# SCH_wiring_diagram_2026-05-13.net
KiCad netlist of a schematic drawn in EasyEDA
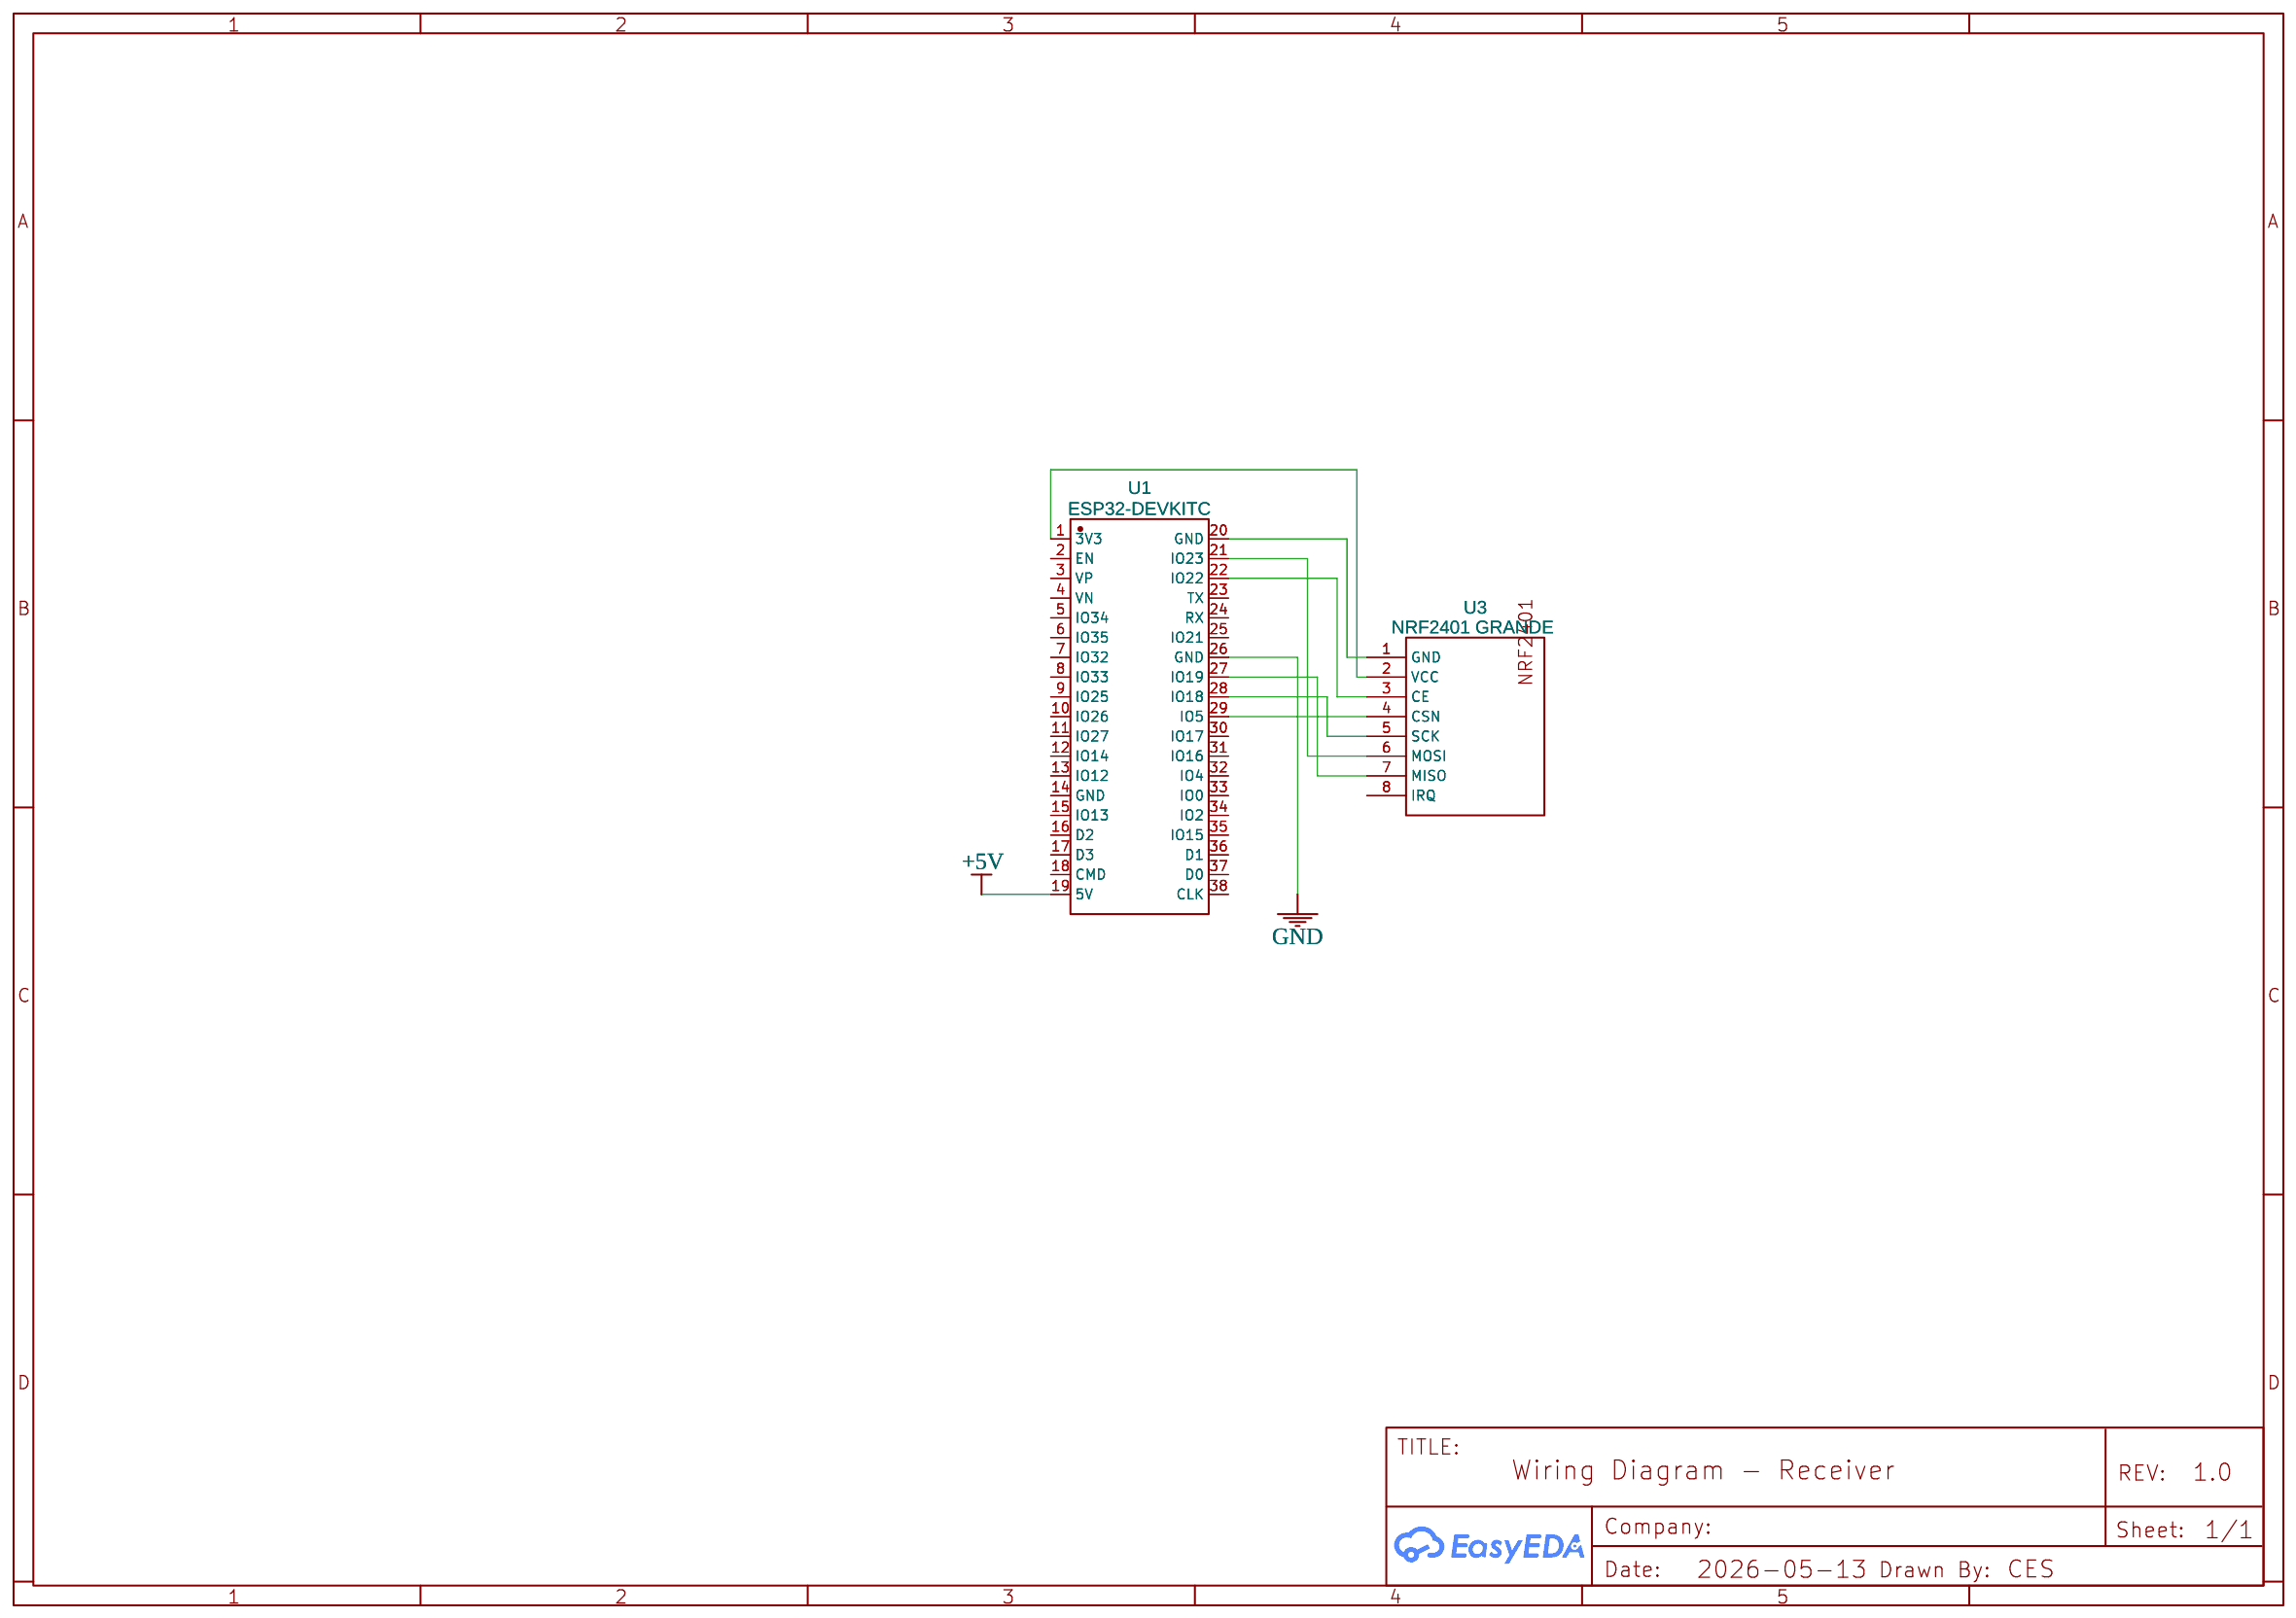
[diagram p0: schematic sheet]

(export (version "E")
  (design (tool "Eeschema 10.0.6"))
  (components
    (comp (ref "U1")
      (value "ESP32-DEVKITC")
      (fields
        (field (name "Manufacturer Part") "ESP32-DevKitC")
        (field (name "Manufacturer") "ESPRESSIF(乐鑫)")
      )
      (libsource (lib "") (part "ESP32-DEVKITC"))
    )
    (comp (ref "U3") (value "NRF2401 GRANDE") (libsource (lib "") (part "NRF2401_GRANDE")))
  )
  (nets
    (net (code "1") (name "+5V") (class "Default")
      (node (ref "U1") (pin "19") (pinfunction "5V_19") (pintype "unspecified"))
    )
    (net (code "2") (name "GND") (class "Default")
      (node (ref "U1") (pin "26") (pinfunction "GND_26") (pintype "unspecified"))
    )
    (net (code "3") (name "Net-(U1-3V3)") (class "Default")
      (node (ref "U1") (pin "1") (pinfunction "3V3_1") (pintype "unspecified"))
      (node (ref "U3") (pin "2") (pinfunction "VCC_2") (pintype "unspecified"))
    )
    (net (code "4") (name "Net-(U1-IO5)") (class "Default")
      (node (ref "U1") (pin "29") (pinfunction "IO5_29") (pintype "unspecified"))
      (node (ref "U3") (pin "4") (pinfunction "CSN_4") (pintype "unspecified"))
    )
    (net (code "5") (name "Net-(U1-IO18)") (class "Default")
      (node (ref "U1") (pin "28") (pinfunction "IO18_28") (pintype "unspecified"))
      (node (ref "U3") (pin "5") (pinfunction "SCK_5") (pintype "unspecified"))
    )
    (net (code "6") (name "Net-(U1-IO19)") (class "Default")
      (node (ref "U1") (pin "27") (pinfunction "IO19_27") (pintype "unspecified"))
      (node (ref "U3") (pin "7") (pinfunction "MISO_7") (pintype "unspecified"))
    )
    (net (code "7") (name "Net-(U1-IO22)") (class "Default")
      (node (ref "U1") (pin "22") (pinfunction "IO22_22") (pintype "unspecified"))
      (node (ref "U3") (pin "3") (pinfunction "CE_3") (pintype "unspecified"))
    )
    (net (code "8") (name "Net-(U1-IO23)") (class "Default")
      (node (ref "U1") (pin "21") (pinfunction "IO23_21") (pintype "unspecified"))
      (node (ref "U3") (pin "6") (pinfunction "MOSI_6") (pintype "unspecified"))
    )
    (net (code "9") (name "Net-(U3-GND)") (class "Default")
      (node (ref "U1") (pin "20") (pinfunction "GND_20") (pintype "unspecified"))
      (node (ref "U3") (pin "1") (pinfunction "GND_1") (pintype "unspecified"))
    )
    (net (code "10") (name "unconnected-(U1-CLK-Pad38)") (class "Default")
      (node (ref "U1") (pin "38") (pinfunction "CLK_38") (pintype "unspecified"))
    )
    (net (code "11") (name "unconnected-(U1-CMD-Pad18)") (class "Default")
      (node (ref "U1") (pin "18") (pinfunction "CMD_18") (pintype "unspecified"))
    )
    (net (code "12") (name "unconnected-(U1-D0-Pad37)") (class "Default")
      (node (ref "U1") (pin "37") (pinfunction "D0_37") (pintype "unspecified"))
    )
    (net (code "13") (name "unconnected-(U1-D1-Pad36)") (class "Default")
      (node (ref "U1") (pin "36") (pinfunction "D1_36") (pintype "unspecified"))
    )
    (net (code "14") (name "unconnected-(U1-D2-Pad16)") (class "Default")
      (node (ref "U1") (pin "16") (pinfunction "D2_16") (pintype "unspecified"))
    )
    (net (code "15") (name "unconnected-(U1-D3-Pad17)") (class "Default")
      (node (ref "U1") (pin "17") (pinfunction "D3_17") (pintype "unspecified"))
    )
    (net (code "16") (name "unconnected-(U1-EN-Pad2)") (class "Default")
      (node (ref "U1") (pin "2") (pinfunction "EN_2") (pintype "unspecified"))
    )
    (net (code "17") (name "unconnected-(U1-GND-Pad14)") (class "Default")
      (node (ref "U1") (pin "14") (pinfunction "GND_14") (pintype "unspecified"))
    )
    (net (code "18") (name "unconnected-(U1-IO0-Pad33)") (class "Default")
      (node (ref "U1") (pin "33") (pinfunction "IO0_33") (pintype "unspecified"))
    )
    (net (code "19") (name "unconnected-(U1-IO2-Pad34)") (class "Default")
      (node (ref "U1") (pin "34") (pinfunction "IO2_34") (pintype "unspecified"))
    )
    (net (code "20") (name "unconnected-(U1-IO4-Pad32)") (class "Default")
      (node (ref "U1") (pin "32") (pinfunction "IO4_32") (pintype "unspecified"))
    )
    (net (code "21") (name "unconnected-(U1-IO12-Pad13)") (class "Default")
      (node (ref "U1") (pin "13") (pinfunction "IO12_13") (pintype "unspecified"))
    )
    (net (code "22") (name "unconnected-(U1-IO13-Pad15)") (class "Default")
      (node (ref "U1") (pin "15") (pinfunction "IO13_15") (pintype "unspecified"))
    )
    (net (code "23") (name "unconnected-(U1-IO14-Pad12)") (class "Default")
      (node (ref "U1") (pin "12") (pinfunction "IO14_12") (pintype "unspecified"))
    )
    (net (code "24") (name "unconnected-(U1-IO15-Pad35)") (class "Default")
      (node (ref "U1") (pin "35") (pinfunction "IO15_35") (pintype "unspecified"))
    )
    (net (code "25") (name "unconnected-(U1-IO16-Pad31)") (class "Default")
      (node (ref "U1") (pin "31") (pinfunction "IO16_31") (pintype "unspecified"))
    )
    (net (code "26") (name "unconnected-(U1-IO17-Pad30)") (class "Default")
      (node (ref "U1") (pin "30") (pinfunction "IO17_30") (pintype "unspecified"))
    )
    (net (code "27") (name "unconnected-(U1-IO21-Pad25)") (class "Default")
      (node (ref "U1") (pin "25") (pinfunction "IO21_25") (pintype "unspecified"))
    )
    (net (code "28") (name "unconnected-(U1-IO25-Pad9)") (class "Default")
      (node (ref "U1") (pin "9") (pinfunction "IO25_9") (pintype "unspecified"))
    )
    (net (code "29") (name "unconnected-(U1-IO26-Pad10)") (class "Default")
      (node (ref "U1") (pin "10") (pinfunction "IO26_10") (pintype "unspecified"))
    )
    (net (code "30") (name "unconnected-(U1-IO27-Pad11)") (class "Default")
      (node (ref "U1") (pin "11") (pinfunction "IO27_11") (pintype "unspecified"))
    )
    (net (code "31") (name "unconnected-(U1-IO32-Pad7)") (class "Default")
      (node (ref "U1") (pin "7") (pinfunction "IO32_7") (pintype "unspecified"))
    )
    (net (code "32") (name "unconnected-(U1-IO33-Pad8)") (class "Default")
      (node (ref "U1") (pin "8") (pinfunction "IO33_8") (pintype "unspecified"))
    )
    (net (code "33") (name "unconnected-(U1-IO34-Pad5)") (class "Default")
      (node (ref "U1") (pin "5") (pinfunction "IO34_5") (pintype "unspecified"))
    )
    (net (code "34") (name "unconnected-(U1-IO35-Pad6)") (class "Default")
      (node (ref "U1") (pin "6") (pinfunction "IO35_6") (pintype "unspecified"))
    )
    (net (code "35") (name "unconnected-(U1-RX-Pad24)") (class "Default")
      (node (ref "U1") (pin "24") (pinfunction "RX_24") (pintype "unspecified"))
    )
    (net (code "36") (name "unconnected-(U1-TX-Pad23)") (class "Default")
      (node (ref "U1") (pin "23") (pinfunction "TX_23") (pintype "unspecified"))
    )
    (net (code "37") (name "unconnected-(U1-VN-Pad4)") (class "Default")
      (node (ref "U1") (pin "4") (pinfunction "VN_4") (pintype "unspecified"))
    )
    (net (code "38") (name "unconnected-(U1-VP-Pad3)") (class "Default")
      (node (ref "U1") (pin "3") (pinfunction "VP_3") (pintype "unspecified"))
    )
    (net (code "39") (name "unconnected-(U3-IRQ-Pad8)") (class "Default")
      (node (ref "U3") (pin "8") (pinfunction "IRQ_8") (pintype "unspecified"))
    )
  )
)
